# basicController.net
KiCad netlist of a schematic drawn in EAGLE
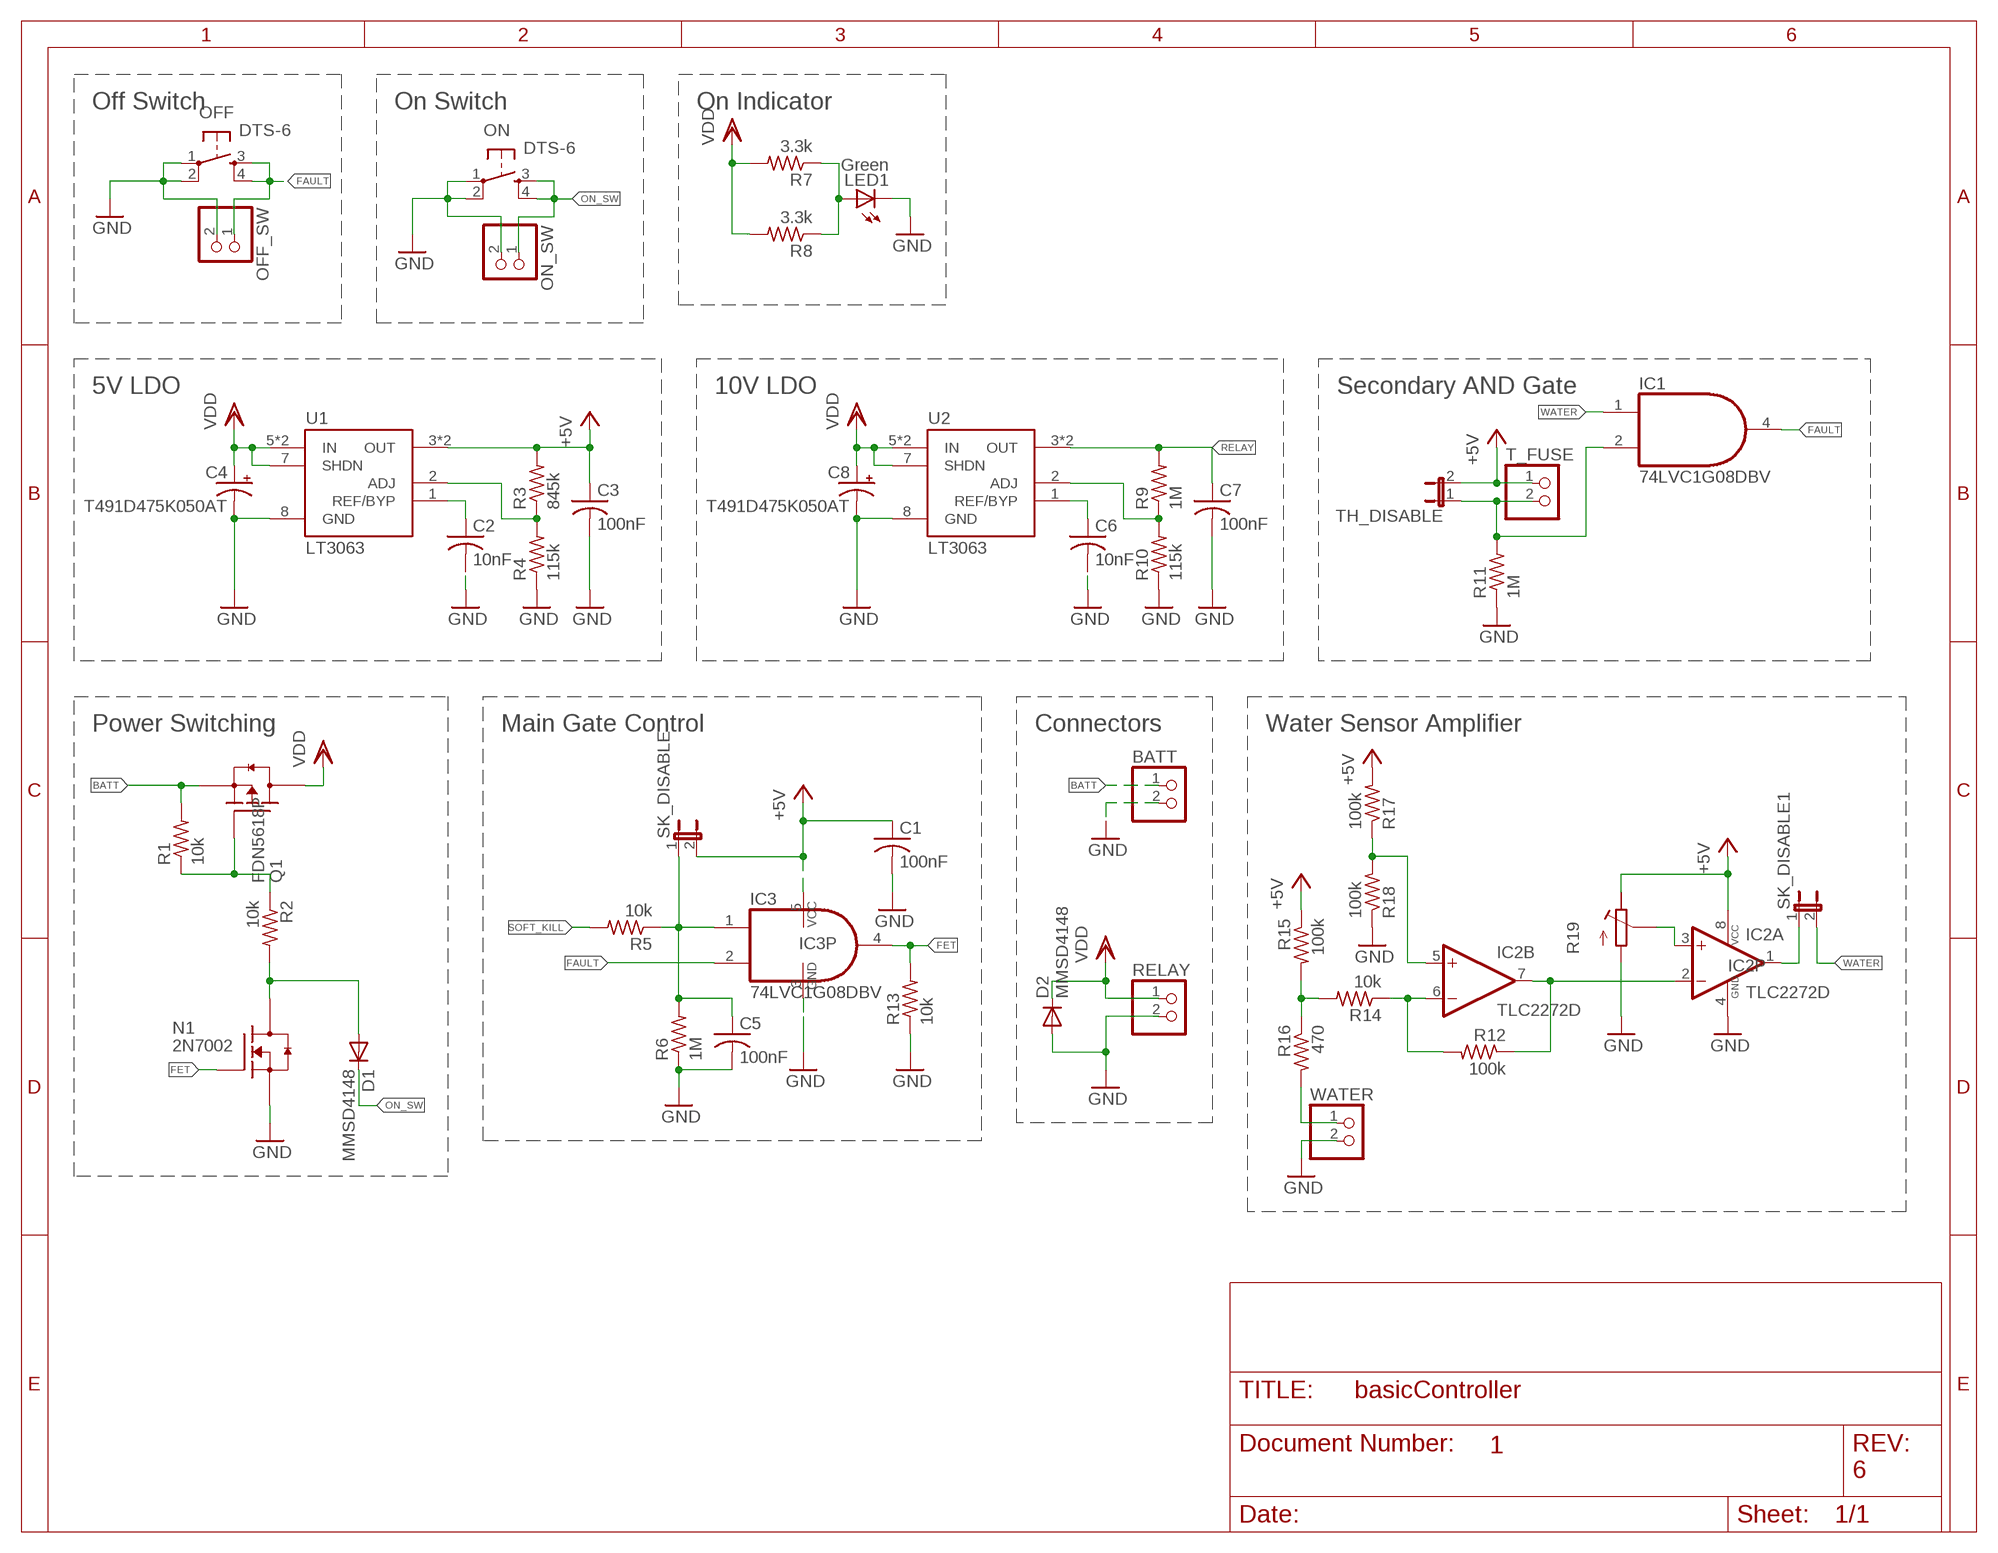
[diagram p0: schematic, sheet 1]

(export (version "E")
  (design (tool "Eeschema 10.0.6"))
  (components
    (comp (ref "BATT")
      (value "PINHD-1X2")
      (footprint "eagle-import:1X02")
      (libsource (lib "eagle-import") (part "PINHD-1X2"))
    )
    (comp (ref "C1")
      (value "100nF")
      (footprint "eagle-import:C0805")
      (libsource (lib "eagle-import") (part "C-USC0805"))
    )
    (comp (ref "C2")
      (value "10nF")
      (footprint "eagle-import:C0805")
      (libsource (lib "eagle-import") (part "C-USC0805"))
    )
    (comp (ref "C3")
      (value "100nF")
      (footprint "eagle-import:C0805")
      (libsource (lib "eagle-import") (part "C-USC0805"))
    )
    (comp (ref "C4")
      (value "T491D475K050AT")
      (footprint "eagle-import:CT7343")
      (libsource (lib "eagle-import") (part "CPOL-USCT7343"))
    )
    (comp (ref "C5")
      (value "100nF")
      (footprint "eagle-import:C0805")
      (libsource (lib "eagle-import") (part "C-USC0805"))
    )
    (comp (ref "C6")
      (value "10nF")
      (footprint "eagle-import:C0805")
      (libsource (lib "eagle-import") (part "C-USC0805"))
    )
    (comp (ref "C7")
      (value "100nF")
      (footprint "eagle-import:C0805")
      (libsource (lib "eagle-import") (part "C-USC0805"))
    )
    (comp (ref "C8")
      (value "T491D475K050AT")
      (footprint "eagle-import:CT7343")
      (libsource (lib "eagle-import") (part "CPOL-USCT7343"))
    )
    (comp (ref "D1")
      (value "MMSD4148")
      (footprint "eagle-import:SOD123")
      (libsource (lib "eagle-import") (part "DIODE-SOD123"))
    )
    (comp (ref "D2")
      (value "MMSD4148")
      (footprint "eagle-import:SOD123")
      (libsource (lib "eagle-import") (part "DIODE-SOD123"))
    )
    (comp (ref "IC1")
      (value "74LVC1G08DBV")
      (footprint "eagle-import:SOT23-5")
      (libsource (lib "eagle-import") (part "741G08DBVLVC"))
    )
    (comp (ref "IC2")
      (value "TLC2272D")
      (footprint "eagle-import:SO-08")
      (libsource (lib "eagle-import") (part "TLC2272D"))
    )
    (comp (ref "IC3")
      (value "74LVC1G08DBV")
      (footprint "eagle-import:SOT23-5")
      (libsource (lib "eagle-import") (part "741G08DBVLVC"))
    )
    (comp (ref "LED1")
      (value "Green")
      (footprint "eagle-import:CHIP-LED0805")
      (libsource (lib "eagle-import") (part "LEDCHIP-LED0805"))
    )
    (comp (ref "N1")
      (value "2N7002")
      (footprint "eagle-import:SOT23")
      (libsource (lib "eagle-import") (part "2N7002"))
    )
    (comp (ref "OFF")
      (value "DTS-6")
      (footprint "eagle-import:DTS-6")
      (libsource (lib "eagle-import") (part "DTS-6"))
    )
    (comp (ref "OFF_SW")
      (value "PINHD-1X2")
      (footprint "eagle-import:1X02")
      (libsource (lib "eagle-import") (part "PINHD-1X2"))
    )
    (comp (ref "ON")
      (value "DTS-6")
      (footprint "eagle-import:DTS-6")
      (libsource (lib "eagle-import") (part "DTS-6"))
    )
    (comp (ref "ON_SW")
      (value "PINHD-1X2")
      (footprint "eagle-import:1X02")
      (libsource (lib "eagle-import") (part "PINHD-1X2"))
    )
    (comp (ref "Q1")
      (value "FDN5618P")
      (footprint "eagle-import:SOT23")
      (libsource (lib "eagle-import") (part "FDN5618P"))
    )
    (comp (ref "R1")
      (value "10k")
      (footprint "eagle-import:R0805")
      (libsource (lib "eagle-import") (part "R-US_R0805"))
    )
    (comp (ref "R2")
      (value "10k")
      (footprint "eagle-import:R0805")
      (libsource (lib "eagle-import") (part "R-US_R0805"))
    )
    (comp (ref "R3")
      (value "845k")
      (footprint "eagle-import:R0805")
      (libsource (lib "eagle-import") (part "R-US_R0805"))
    )
    (comp (ref "R4")
      (value "115k")
      (footprint "eagle-import:R0805")
      (libsource (lib "eagle-import") (part "R-US_R0805"))
    )
    (comp (ref "R5")
      (value "10k")
      (footprint "eagle-import:R0805")
      (libsource (lib "eagle-import") (part "R-US_R0805"))
    )
    (comp (ref "R6")
      (value "1M")
      (footprint "eagle-import:R0805")
      (libsource (lib "eagle-import") (part "R-US_R0805"))
    )
    (comp (ref "R7")
      (value "3.3k")
      (footprint "eagle-import:R0805")
      (libsource (lib "eagle-import") (part "R-US_R0805"))
    )
    (comp (ref "R8")
      (value "3.3k")
      (footprint "eagle-import:R0805")
      (libsource (lib "eagle-import") (part "R-US_R0805"))
    )
    (comp (ref "R9")
      (value "1M")
      (footprint "eagle-import:R0805")
      (libsource (lib "eagle-import") (part "R-US_R0805"))
    )
    (comp (ref "R10")
      (value "115k")
      (footprint "eagle-import:R0805")
      (libsource (lib "eagle-import") (part "R-US_R0805"))
    )
    (comp (ref "R11")
      (value "1M")
      (footprint "eagle-import:R0805")
      (libsource (lib "eagle-import") (part "R-US_R0805"))
    )
    (comp (ref "R12")
      (value "100k")
      (footprint "eagle-import:R0805")
      (libsource (lib "eagle-import") (part "R-US_R0805"))
    )
    (comp (ref "R13")
      (value "10k")
      (footprint "eagle-import:R0805")
      (libsource (lib "eagle-import") (part "R-US_R0805"))
    )
    (comp (ref "R14")
      (value "10k")
      (footprint "eagle-import:R0805")
      (libsource (lib "eagle-import") (part "R-US_R0805"))
    )
    (comp (ref "R15")
      (value "100k")
      (footprint "eagle-import:R0805")
      (libsource (lib "eagle-import") (part "R-US_R0805"))
    )
    (comp (ref "R16")
      (value "470")
      (footprint "eagle-import:R0805")
      (libsource (lib "eagle-import") (part "R-US_R0805"))
    )
    (comp (ref "R17")
      (value "100k")
      (footprint "eagle-import:R0805")
      (libsource (lib "eagle-import") (part "R-US_R0805"))
    )
    (comp (ref "R18")
      (value "100k")
      (footprint "eagle-import:R0805")
      (libsource (lib "eagle-import") (part "R-US_R0805"))
    )
    (comp (ref "R19")
      (value "R-TRIMM3314J")
      (footprint "eagle-import:RTRIM3314J")
      (libsource (lib "eagle-import") (part "R-TRIMM3314J"))
    )
    (comp (ref "RELAY")
      (value "PINHD-1X2")
      (footprint "eagle-import:1X02")
      (libsource (lib "eagle-import") (part "PINHD-1X2"))
    )
    (comp (ref "SK_DISABLE")
      (value "JP1E")
      (footprint "eagle-import:JP1")
      (libsource (lib "eagle-import") (part "JP1E"))
    )
    (comp (ref "SK_DISABLE1")
      (value "JP1E")
      (footprint "eagle-import:JP1")
      (libsource (lib "eagle-import") (part "JP1E"))
    )
    (comp (ref "TH_DISABLE")
      (value "JP1E")
      (footprint "eagle-import:JP1")
      (libsource (lib "eagle-import") (part "JP1E"))
    )
    (comp (ref "T_FUSE")
      (value "PINHD-1X2")
      (footprint "eagle-import:1X02")
      (libsource (lib "eagle-import") (part "PINHD-1X2"))
    )
    (comp (ref "U1")
      (value "LT3063")
      (footprint "eagle-import:MSOP8")
      (libsource (lib "eagle-import") (part "LT3063"))
    )
    (comp (ref "U2")
      (value "LT3063")
      (footprint "eagle-import:MSOP8")
      (libsource (lib "eagle-import") (part "LT3063"))
    )
    (comp (ref "WATER")
      (value "PINHD-1X2")
      (footprint "eagle-import:1X02")
      (libsource (lib "eagle-import") (part "PINHD-1X2"))
    )
  )
  (nets
    (net (code "1") (name "+5V") (class "Default")
      (node (ref "C1") (pin "1") (pinfunction "1_1") (pintype "passive"))
      (node (ref "C3") (pin "1") (pinfunction "1_1") (pintype "passive"))
      (node (ref "IC2") (pin "8") (pinfunction "VCC_8") (pintype "power_in"))
      (node (ref "IC3") (pin "5") (pinfunction "VCC_5") (pintype "power_in"))
      (node (ref "R15") (pin "1") (pinfunction "1_1") (pintype "passive"))
      (node (ref "R17") (pin "2") (pinfunction "2_2") (pintype "passive"))
      (node (ref "R19") (pin "3") (pinfunction "A_3") (pintype "passive"))
      (node (ref "R3") (pin "2") (pinfunction "2_2") (pintype "passive"))
      (node (ref "SK_DISABLE") (pin "2") (pinfunction "2_2") (pintype "passive"))
      (node (ref "TH_DISABLE") (pin "2") (pinfunction "2_2") (pintype "passive"))
      (node (ref "T_FUSE") (pin "1") (pinfunction "1_1") (pintype "passive"))
      (node (ref "U1") (pin "3") (pinfunction "OUT_3") (pintype "bidirectional"))
      (node (ref "U1") (pin "4") (pinfunction "OUT_4") (pintype "bidirectional"))
    )
    (net (code "2") (name "BATT") (class "Default")
      (node (ref "BATT") (pin "1") (pinfunction "1_1") (pintype "passive"))
      (node (ref "Q1") (pin "2") (pinfunction "S_2") (pintype "passive"))
      (node (ref "R1") (pin "2") (pinfunction "2_2") (pintype "passive"))
    )
    (net (code "3") (name "FAULT") (class "Default")
      (node (ref "IC1") (pin "4") (pinfunction "O_4") (pintype "output"))
      (node (ref "IC3") (pin "2") (pinfunction "I1_2") (pintype "input"))
      (node (ref "OFF") (pin "3") (pinfunction "3_3") (pintype "passive"))
      (node (ref "OFF") (pin "4") (pinfunction "4_4") (pintype "passive"))
      (node (ref "OFF_SW") (pin "1") (pinfunction "1_1") (pintype "passive"))
    )
    (net (code "4") (name "FET") (class "Default")
      (node (ref "IC3") (pin "4") (pinfunction "O_4") (pintype "output"))
      (node (ref "N1") (pin "1") (pinfunction "G_1") (pintype "passive"))
      (node (ref "R13") (pin "2") (pinfunction "2_2") (pintype "passive"))
    )
    (net (code "5") (name "GND") (class "Default")
      (node (ref "BATT") (pin "2") (pinfunction "2_2") (pintype "passive"))
      (node (ref "C1") (pin "2") (pinfunction "2_2") (pintype "passive"))
      (node (ref "C2") (pin "2") (pinfunction "2_2") (pintype "passive"))
      (node (ref "C3") (pin "2") (pinfunction "2_2") (pintype "passive"))
      (node (ref "C4") (pin "-") (pinfunction "-_-") (pintype "passive"))
      (node (ref "C5") (pin "2") (pinfunction "2_2") (pintype "passive"))
      (node (ref "C6") (pin "2") (pinfunction "2_2") (pintype "passive"))
      (node (ref "C7") (pin "2") (pinfunction "2_2") (pintype "passive"))
      (node (ref "C8") (pin "-") (pinfunction "-_-") (pintype "passive"))
      (node (ref "D2") (pin "A") (pinfunction "A_A") (pintype "passive"))
      (node (ref "IC2") (pin "4") (pinfunction "GND_4") (pintype "power_in"))
      (node (ref "IC3") (pin "3") (pinfunction "GND_3") (pintype "power_in"))
      (node (ref "LED1") (pin "C") (pinfunction "C_C") (pintype "passive"))
      (node (ref "N1") (pin "2") (pinfunction "S_2") (pintype "passive"))
      (node (ref "OFF") (pin "1") (pinfunction "1_1") (pintype "passive"))
      (node (ref "OFF") (pin "2") (pinfunction "2_2") (pintype "passive"))
      (node (ref "OFF_SW") (pin "2") (pinfunction "2_2") (pintype "passive"))
      (node (ref "ON") (pin "1") (pinfunction "1_1") (pintype "passive"))
      (node (ref "ON") (pin "2") (pinfunction "2_2") (pintype "passive"))
      (node (ref "ON_SW") (pin "2") (pinfunction "2_2") (pintype "passive"))
      (node (ref "R10") (pin "1") (pinfunction "1_1") (pintype "passive"))
      (node (ref "R11") (pin "1") (pinfunction "1_1") (pintype "passive"))
      (node (ref "R13") (pin "1") (pinfunction "1_1") (pintype "passive"))
      (node (ref "R18") (pin "1") (pinfunction "1_1") (pintype "passive"))
      (node (ref "R19") (pin "1") (pinfunction "E_1") (pintype "passive"))
      (node (ref "R4") (pin "1") (pinfunction "1_1") (pintype "passive"))
      (node (ref "R6") (pin "1") (pinfunction "1_1") (pintype "passive"))
      (node (ref "RELAY") (pin "2") (pinfunction "2_2") (pintype "passive"))
      (node (ref "U1") (pin "8") (pinfunction "GND_8") (pintype "bidirectional"))
      (node (ref "U2") (pin "8") (pinfunction "GND_8") (pintype "bidirectional"))
      (node (ref "WATER") (pin "2") (pinfunction "2_2") (pintype "passive"))
    )
    (net (code "6") (name "Net-(IC1A-I1)") (class "Default")
      (node (ref "IC1") (pin "2") (pinfunction "I1_2") (pintype "input"))
      (node (ref "R11") (pin "2") (pinfunction "2_2") (pintype "passive"))
      (node (ref "TH_DISABLE") (pin "1") (pinfunction "1_1") (pintype "passive"))
      (node (ref "T_FUSE") (pin "2") (pinfunction "2_2") (pintype "passive"))
    )
    (net (code "7") (name "Net-(IC2A-+IN)") (class "Default")
      (node (ref "IC2") (pin "3") (pinfunction "+IN_3") (pintype "input"))
      (node (ref "R19") (pin "2") (pinfunction "S_2") (pintype "passive"))
    )
    (net (code "8") (name "Net-(IC2A--IN)") (class "Default")
      (node (ref "IC2") (pin "2") (pinfunction "-IN_2") (pintype "input"))
      (node (ref "IC2") (pin "7") (pinfunction "OUT_7") (pintype "output"))
      (node (ref "R12") (pin "1") (pinfunction "1_1") (pintype "passive"))
    )
    (net (code "9") (name "Net-(IC2A-OUT)") (class "Default")
      (node (ref "IC2") (pin "1") (pinfunction "OUT_1") (pintype "output"))
      (node (ref "SK_DISABLE1") (pin "1") (pinfunction "1_1") (pintype "passive"))
    )
    (net (code "10") (name "Net-(IC2B-+IN)") (class "Default")
      (node (ref "IC2") (pin "5") (pinfunction "+IN_5") (pintype "input"))
      (node (ref "R17") (pin "1") (pinfunction "1_1") (pintype "passive"))
      (node (ref "R18") (pin "2") (pinfunction "2_2") (pintype "passive"))
    )
    (net (code "11") (name "Net-(IC2B--IN)") (class "Default")
      (node (ref "IC2") (pin "6") (pinfunction "-IN_6") (pintype "input"))
      (node (ref "R12") (pin "2") (pinfunction "2_2") (pintype "passive"))
      (node (ref "R14") (pin "1") (pinfunction "1_1") (pintype "passive"))
    )
    (net (code "12") (name "Net-(IC3A-I0)") (class "Default")
      (node (ref "C5") (pin "1") (pinfunction "1_1") (pintype "passive"))
      (node (ref "IC3") (pin "1") (pinfunction "I0_1") (pintype "input"))
      (node (ref "R5") (pin "1") (pinfunction "1_1") (pintype "passive"))
      (node (ref "R6") (pin "2") (pinfunction "2_2") (pintype "passive"))
      (node (ref "SK_DISABLE") (pin "1") (pinfunction "1_1") (pintype "passive"))
    )
    (net (code "13") (name "Net-(LED1-PadA)") (class "Default")
      (node (ref "LED1") (pin "A") (pinfunction "A_A") (pintype "passive"))
      (node (ref "R7") (pin "1") (pinfunction "1_1") (pintype "passive"))
      (node (ref "R8") (pin "1") (pinfunction "1_1") (pintype "passive"))
    )
    (net (code "14") (name "Net-(N1-D)") (class "Default")
      (node (ref "D1") (pin "A") (pinfunction "A_A") (pintype "passive"))
      (node (ref "N1") (pin "3") (pinfunction "D_3") (pintype "bidirectional"))
      (node (ref "R2") (pin "2") (pinfunction "2_2") (pintype "passive"))
    )
    (net (code "15") (name "Net-(Q1-G)") (class "Default")
      (node (ref "Q1") (pin "1") (pinfunction "G_1") (pintype "passive"))
      (node (ref "R1") (pin "1") (pinfunction "1_1") (pintype "passive"))
      (node (ref "R2") (pin "1") (pinfunction "1_1") (pintype "passive"))
    )
    (net (code "16") (name "Net-(R14-Pad2)") (class "Default")
      (node (ref "R14") (pin "2") (pinfunction "2_2") (pintype "passive"))
      (node (ref "R15") (pin "2") (pinfunction "2_2") (pintype "passive"))
      (node (ref "R16") (pin "1") (pinfunction "1_1") (pintype "passive"))
    )
    (net (code "17") (name "Net-(R16-Pad2)") (class "Default")
      (node (ref "R16") (pin "2") (pinfunction "2_2") (pintype "passive"))
      (node (ref "WATER") (pin "1") (pinfunction "1_1") (pintype "passive"))
    )
    (net (code "18") (name "Net-(U1-ADJ)") (class "Default")
      (node (ref "R3") (pin "1") (pinfunction "1_1") (pintype "passive"))
      (node (ref "R4") (pin "2") (pinfunction "2_2") (pintype "passive"))
      (node (ref "U1") (pin "2") (pinfunction "ADJ_2") (pintype "bidirectional"))
    )
    (net (code "19") (name "Net-(U1-REF{slash}BYP)") (class "Default")
      (node (ref "C2") (pin "1") (pinfunction "1_1") (pintype "passive"))
      (node (ref "U1") (pin "1") (pinfunction "REF/BYP_1") (pintype "bidirectional"))
    )
    (net (code "20") (name "Net-(U2-ADJ)") (class "Default")
      (node (ref "R10") (pin "2") (pinfunction "2_2") (pintype "passive"))
      (node (ref "R9") (pin "1") (pinfunction "1_1") (pintype "passive"))
      (node (ref "U2") (pin "2") (pinfunction "ADJ_2") (pintype "bidirectional"))
    )
    (net (code "21") (name "Net-(U2-REF{slash}BYP)") (class "Default")
      (node (ref "C6") (pin "1") (pinfunction "1_1") (pintype "passive"))
      (node (ref "U2") (pin "1") (pinfunction "REF/BYP_1") (pintype "bidirectional"))
    )
    (net (code "22") (name "ON_SW") (class "Default")
      (node (ref "D1") (pin "C") (pinfunction "C_C") (pintype "passive"))
      (node (ref "ON") (pin "3") (pinfunction "3_3") (pintype "passive"))
      (node (ref "ON") (pin "4") (pinfunction "4_4") (pintype "passive"))
      (node (ref "ON_SW") (pin "1") (pinfunction "1_1") (pintype "passive"))
    )
    (net (code "23") (name "RELAY") (class "Default")
      (node (ref "C7") (pin "1") (pinfunction "1_1") (pintype "passive"))
      (node (ref "R9") (pin "2") (pinfunction "2_2") (pintype "passive"))
      (node (ref "U2") (pin "3") (pinfunction "OUT_3") (pintype "bidirectional"))
      (node (ref "U2") (pin "4") (pinfunction "OUT_4") (pintype "bidirectional"))
    )
    (net (code "24") (name "SOFT_KILL") (class "Default")
      (node (ref "R5") (pin "2") (pinfunction "2_2") (pintype "passive"))
    )
    (net (code "25") (name "VDD") (class "Default")
      (node (ref "C4") (pin "+") (pinfunction "+_+") (pintype "passive"))
      (node (ref "C8") (pin "+") (pinfunction "+_+") (pintype "passive"))
      (node (ref "D2") (pin "C") (pinfunction "C_C") (pintype "passive"))
      (node (ref "Q1") (pin "3") (pinfunction "D_3") (pintype "passive"))
      (node (ref "R7") (pin "2") (pinfunction "2_2") (pintype "passive"))
      (node (ref "R8") (pin "2") (pinfunction "2_2") (pintype "passive"))
      (node (ref "RELAY") (pin "1") (pinfunction "1_1") (pintype "passive"))
      (node (ref "U1") (pin "5") (pinfunction "IN_5") (pintype "bidirectional"))
      (node (ref "U1") (pin "6") (pinfunction "IN_6") (pintype "bidirectional"))
      (node (ref "U1") (pin "7") (pinfunction "SHDN_7") (pintype "bidirectional"))
      (node (ref "U2") (pin "5") (pinfunction "IN_5") (pintype "bidirectional"))
      (node (ref "U2") (pin "6") (pinfunction "IN_6") (pintype "bidirectional"))
      (node (ref "U2") (pin "7") (pinfunction "SHDN_7") (pintype "bidirectional"))
    )
    (net (code "26") (name "WATER") (class "Default")
      (node (ref "IC1") (pin "1") (pinfunction "I0_1") (pintype "input"))
      (node (ref "SK_DISABLE1") (pin "2") (pinfunction "2_2") (pintype "passive"))
    )
  )
)
